# ACBoard.net
KiCad netlist of a schematic drawn in EAGLE
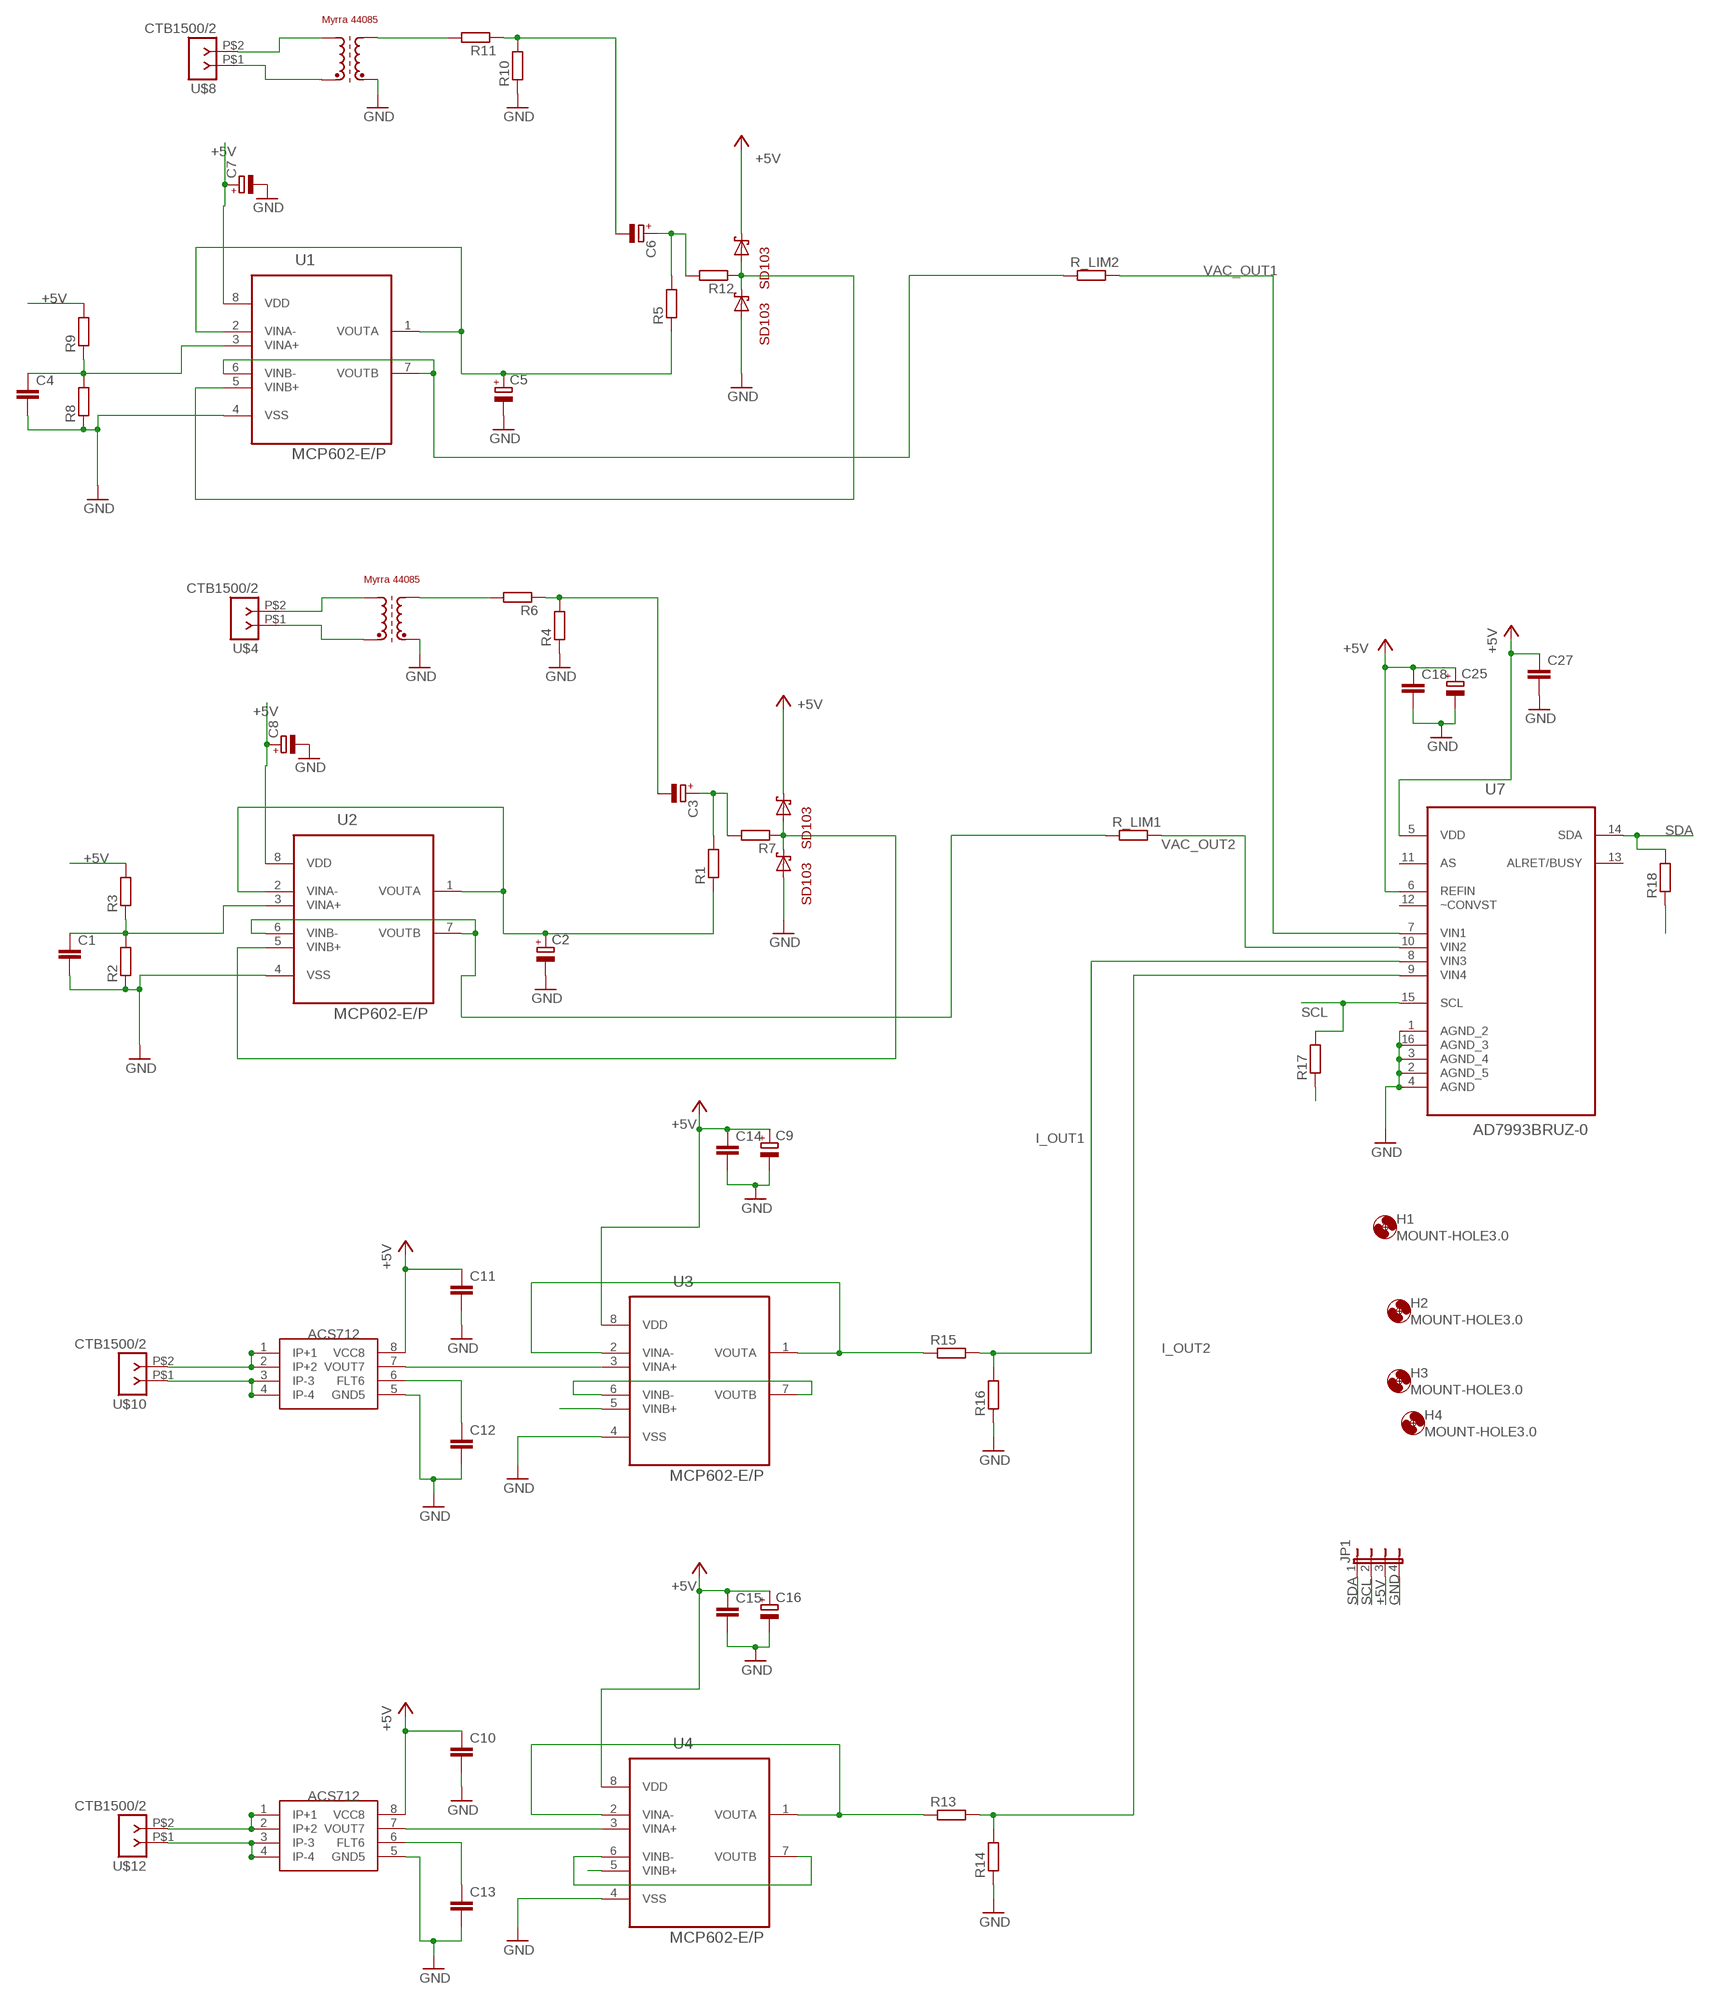
[diagram p0: schematic, sheet 1]

(export (version "E")
  (design (tool "Eeschema 10.0.6"))
  (components
    (comp (ref "C1")
      (value "C5P")
      (footprint "eagle-import:C050-030-075")
      (libsource (lib "eagle-import") (part "C5P"))
    )
    (comp (ref "C2")
      (value "CPOL1")
      (footprint "eagle-import:E2,5-7---100UF")
      (libsource (lib "eagle-import") (part "CPOL1"))
    )
    (comp (ref "C3")
      (value "CPOL1")
      (footprint "eagle-import:E2,5-7---100UF")
      (libsource (lib "eagle-import") (part "CPOL1"))
    )
    (comp (ref "C4")
      (value "C5P")
      (footprint "eagle-import:C050-030-075")
      (libsource (lib "eagle-import") (part "C5P"))
    )
    (comp (ref "C5")
      (value "CPOL1")
      (footprint "eagle-import:E2,5-7---100UF")
      (libsource (lib "eagle-import") (part "CPOL1"))
    )
    (comp (ref "C6")
      (value "CPOL1")
      (footprint "eagle-import:E2,5-7---100UF")
      (libsource (lib "eagle-import") (part "CPOL1"))
    )
    (comp (ref "C7")
      (value "CPOL1")
      (footprint "eagle-import:E2,5-7---100UF")
      (libsource (lib "eagle-import") (part "CPOL1"))
    )
    (comp (ref "C8")
      (value "CPOL1")
      (footprint "eagle-import:E2,5-7---100UF")
      (libsource (lib "eagle-import") (part "CPOL1"))
    )
    (comp (ref "C9")
      (value "CPOL-EUE2-4")
      (footprint "eagle-import:E2-4")
      (libsource (lib "eagle-import") (part "CPOL-EUE2-4"))
    )
    (comp (ref "C10")
      (value "C-EU025-024X044")
      (footprint "eagle-import:C025-024X044")
      (libsource (lib "eagle-import") (part "C-EU025-024X044"))
    )
    (comp (ref "C11")
      (value "C-EU025-024X044")
      (footprint "eagle-import:C025-024X044")
      (libsource (lib "eagle-import") (part "C-EU025-024X044"))
    )
    (comp (ref "C12")
      (value "C-EU025-024X044")
      (footprint "eagle-import:C025-024X044")
      (libsource (lib "eagle-import") (part "C-EU025-024X044"))
    )
    (comp (ref "C13")
      (value "C-EU025-024X044")
      (footprint "eagle-import:C025-024X044")
      (libsource (lib "eagle-import") (part "C-EU025-024X044"))
    )
    (comp (ref "C14")
      (value "C-EU025-024X044")
      (footprint "eagle-import:C025-024X044")
      (libsource (lib "eagle-import") (part "C-EU025-024X044"))
    )
    (comp (ref "C15")
      (value "C-EU025-024X044")
      (footprint "eagle-import:C025-024X044")
      (libsource (lib "eagle-import") (part "C-EU025-024X044"))
    )
    (comp (ref "C16")
      (value "CPOL-EUE2-4")
      (footprint "eagle-import:E2-4")
      (libsource (lib "eagle-import") (part "CPOL-EUE2-4"))
    )
    (comp (ref "C18")
      (value "C-EU025-024X044")
      (footprint "eagle-import:C025-024X044")
      (libsource (lib "eagle-import") (part "C-EU025-024X044"))
    )
    (comp (ref "C25")
      (value "CPOL-EUE2-4")
      (footprint "eagle-import:E2-4")
      (libsource (lib "eagle-import") (part "CPOL-EUE2-4"))
    )
    (comp (ref "C27")
      (value "C-EU025-025X050")
      (footprint "eagle-import:C025-025X050")
      (libsource (lib "eagle-import") (part "C-EU025-025X050"))
    )
    (comp (ref "H1")
      (value "MOUNT-HOLE3.0")
      (footprint "eagle-import:3,0")
      (libsource (lib "eagle-import") (part "MOUNT-HOLE3.0"))
    )
    (comp (ref "H2")
      (value "MOUNT-HOLE3.0")
      (footprint "eagle-import:3,0")
      (libsource (lib "eagle-import") (part "MOUNT-HOLE3.0"))
    )
    (comp (ref "H3")
      (value "MOUNT-HOLE3.0")
      (footprint "eagle-import:3,0")
      (libsource (lib "eagle-import") (part "MOUNT-HOLE3.0"))
    )
    (comp (ref "H4")
      (value "MOUNT-HOLE3.0")
      (footprint "eagle-import:3,0")
      (libsource (lib "eagle-import") (part "MOUNT-HOLE3.0"))
    )
    (comp (ref "JP1")
      (value "JP4E")
      (footprint "eagle-import:JP4")
      (libsource (lib "eagle-import") (part "JP4E"))
    )
    (comp (ref "R1")
      (value "R")
      (footprint "eagle-import:0207_10")
      (libsource (lib "eagle-import") (part "R"))
    )
    (comp (ref "R2")
      (value "R")
      (footprint "eagle-import:0207_10")
      (libsource (lib "eagle-import") (part "R"))
    )
    (comp (ref "R3")
      (value "R")
      (footprint "eagle-import:0207_10")
      (libsource (lib "eagle-import") (part "R"))
    )
    (comp (ref "R4")
      (value "R")
      (footprint "eagle-import:0207_10")
      (libsource (lib "eagle-import") (part "R"))
    )
    (comp (ref "R5")
      (value "R")
      (footprint "eagle-import:0207_10")
      (libsource (lib "eagle-import") (part "R"))
    )
    (comp (ref "R6")
      (value "R")
      (footprint "eagle-import:0207_10")
      (libsource (lib "eagle-import") (part "R"))
    )
    (comp (ref "R7")
      (value "R")
      (footprint "eagle-import:0207_10")
      (libsource (lib "eagle-import") (part "R"))
    )
    (comp (ref "R8")
      (value "R")
      (footprint "eagle-import:0207_10")
      (libsource (lib "eagle-import") (part "R"))
    )
    (comp (ref "R9")
      (value "R")
      (footprint "eagle-import:0207_10")
      (libsource (lib "eagle-import") (part "R"))
    )
    (comp (ref "R10")
      (value "R")
      (footprint "eagle-import:0207_10")
      (libsource (lib "eagle-import") (part "R"))
    )
    (comp (ref "R11")
      (value "R")
      (footprint "eagle-import:0207_10")
      (libsource (lib "eagle-import") (part "R"))
    )
    (comp (ref "R12")
      (value "R")
      (footprint "eagle-import:0207_10")
      (libsource (lib "eagle-import") (part "R"))
    )
    (comp (ref "R13")
      (value "R-EU_0207/7")
      (footprint "eagle-import:0207_7")
      (libsource (lib "eagle-import") (part "R-EU_0207/7"))
    )
    (comp (ref "R14")
      (value "R-EU_0207/7")
      (footprint "eagle-import:0207_7")
      (libsource (lib "eagle-import") (part "R-EU_0207/7"))
    )
    (comp (ref "R15")
      (value "R-EU_0207/7")
      (footprint "eagle-import:0207_7")
      (libsource (lib "eagle-import") (part "R-EU_0207/7"))
    )
    (comp (ref "R16")
      (value "R-EU_0207/7")
      (footprint "eagle-import:0207_7")
      (libsource (lib "eagle-import") (part "R-EU_0207/7"))
    )
    (comp (ref "R17")
      (value "R-EU_0207/7")
      (footprint "eagle-import:0207_7")
      (libsource (lib "eagle-import") (part "R-EU_0207/7"))
    )
    (comp (ref "R18")
      (value "R-EU_0207/7")
      (footprint "eagle-import:0207_7")
      (libsource (lib "eagle-import") (part "R-EU_0207/7"))
    )
    (comp (ref "R_LIM1")
      (value "R")
      (footprint "eagle-import:0207_10")
      (libsource (lib "eagle-import") (part "R"))
    )
    (comp (ref "R_LIM2")
      (value "R")
      (footprint "eagle-import:0207_10")
      (libsource (lib "eagle-import") (part "R"))
    )
    (comp (ref "U$1")
      (value "MYRRA_4408")
      (footprint "eagle-import:4408")
      (libsource (lib "eagle-import") (part "MYRRA_4408"))
    )
    (comp (ref "U$2")
      (value "SD103A")
      (footprint "eagle-import:D035-10")
      (libsource (lib "eagle-import") (part "SD103A"))
    )
    (comp (ref "U$3")
      (value "SD103A")
      (footprint "eagle-import:D035-10")
      (libsource (lib "eagle-import") (part "SD103A"))
    )
    (comp (ref "U$4")
      (value "CTB1500/2")
      (footprint "eagle-import:CTB1500-2")
      (libsource (lib "eagle-import") (part "CTB1500/2"))
    )
    (comp (ref "U$5")
      (value "MYRRA_4408")
      (footprint "eagle-import:4408")
      (libsource (lib "eagle-import") (part "MYRRA_4408"))
    )
    (comp (ref "U$6")
      (value "SD103A")
      (footprint "eagle-import:D035-10")
      (libsource (lib "eagle-import") (part "SD103A"))
    )
    (comp (ref "U$7")
      (value "SD103A")
      (footprint "eagle-import:D035-10")
      (libsource (lib "eagle-import") (part "SD103A"))
    )
    (comp (ref "U$8")
      (value "CTB1500/2")
      (footprint "eagle-import:CTB1500-2")
      (libsource (lib "eagle-import") (part "CTB1500/2"))
    )
    (comp (ref "U$9")
      (value "ACS712")
      (footprint "eagle-import:SO8")
      (libsource (lib "eagle-import") (part "ACS712"))
    )
    (comp (ref "U$10")
      (value "CTB1500/2")
      (footprint "eagle-import:CTB1500-2")
      (libsource (lib "eagle-import") (part "CTB1500/2"))
    )
    (comp (ref "U$11")
      (value "ACS712")
      (footprint "eagle-import:SO8")
      (libsource (lib "eagle-import") (part "ACS712"))
    )
    (comp (ref "U$12")
      (value "CTB1500/2")
      (footprint "eagle-import:CTB1500-2")
      (libsource (lib "eagle-import") (part "CTB1500/2"))
    )
    (comp (ref "U1")
      (value "MCP602-E/P")
      (footprint "eagle-import:DIP254P762X508-8P")
      (libsource (lib "eagle-import") (part "MCP602-E/P"))
    )
    (comp (ref "U2")
      (value "MCP602-E/P")
      (footprint "eagle-import:DIP254P762X508-8P")
      (libsource (lib "eagle-import") (part "MCP602-E/P"))
    )
    (comp (ref "U3")
      (value "MCP602-E/P")
      (footprint "eagle-import:DIP254P762X508-8P")
      (libsource (lib "eagle-import") (part "MCP602-E/P"))
    )
    (comp (ref "U4")
      (value "MCP602-E/P")
      (footprint "eagle-import:DIP254P762X508-8P")
      (libsource (lib "eagle-import") (part "MCP602-E/P"))
    )
    (comp (ref "U7")
      (value "AD7993BRUZ-0")
      (footprint "eagle-import:SOP65P640X120-16N")
      (libsource (lib "eagle-import") (part "AD7993BRUZ-0"))
    )
  )
  (nets
    (net (code "1") (name "+3V3") (class "Default")
      (node (ref "C10") (pin "1") (pinfunction "1_1") (pintype "passive"))
      (node (ref "C11") (pin "1") (pinfunction "1_1") (pintype "passive"))
      (node (ref "C14") (pin "1") (pinfunction "1_1") (pintype "passive"))
      (node (ref "C15") (pin "1") (pinfunction "1_1") (pintype "passive"))
      (node (ref "C16") (pin "+") (pinfunction "+_+") (pintype "passive"))
      (node (ref "C18") (pin "1") (pinfunction "1_1") (pintype "passive"))
      (node (ref "C25") (pin "+") (pinfunction "+_+") (pintype "passive"))
      (node (ref "C27") (pin "1") (pinfunction "1_1") (pintype "passive"))
      (node (ref "C7") (pin "+") (pinfunction "+_+") (pintype "passive"))
      (node (ref "C8") (pin "+") (pinfunction "+_+") (pintype "passive"))
      (node (ref "C9") (pin "+") (pinfunction "+_+") (pintype "passive"))
      (node (ref "JP1") (pin "3") (pinfunction "3_3") (pintype "passive"))
      (node (ref "R17") (pin "1") (pinfunction "1_1") (pintype "passive"))
      (node (ref "R18") (pin "1") (pinfunction "1_1") (pintype "passive"))
      (node (ref "R3") (pin "2") (pinfunction "2_2") (pintype "passive"))
      (node (ref "R9") (pin "2") (pinfunction "2_2") (pintype "passive"))
      (node (ref "U$11") (pin "8") (pinfunction "VCC8_8") (pintype "power_in"))
      (node (ref "U$2") (pin "C") (pinfunction "C_C") (pintype "passive"))
      (node (ref "U$6") (pin "C") (pinfunction "C_C") (pintype "passive"))
      (node (ref "U$9") (pin "8") (pinfunction "VCC8_8") (pintype "power_in"))
      (node (ref "U1") (pin "8") (pinfunction "VDD_8") (pintype "power_in"))
      (node (ref "U2") (pin "8") (pinfunction "VDD_8") (pintype "power_in"))
      (node (ref "U3") (pin "8") (pinfunction "VDD_8") (pintype "power_in"))
      (node (ref "U4") (pin "8") (pinfunction "VDD_8") (pintype "power_in"))
      (node (ref "U7") (pin "5") (pinfunction "VDD_5") (pintype "power_in"))
      (node (ref "U7") (pin "6") (pinfunction "REFIN_6") (pintype "input"))
    )
    (net (code "2") (name "/I_OUT1") (class "Default")
      (node (ref "R15") (pin "2") (pinfunction "2_2") (pintype "passive"))
      (node (ref "R16") (pin "2") (pinfunction "2_2") (pintype "passive"))
      (node (ref "U7") (pin "8") (pinfunction "VIN3_8") (pintype "input"))
    )
    (net (code "3") (name "/I_OUT2") (class "Default")
      (node (ref "R13") (pin "2") (pinfunction "2_2") (pintype "passive"))
      (node (ref "R14") (pin "2") (pinfunction "2_2") (pintype "passive"))
      (node (ref "U7") (pin "9") (pinfunction "VIN4_9") (pintype "input"))
    )
    (net (code "4") (name "/SCL") (class "Default")
      (node (ref "JP1") (pin "2") (pinfunction "2_2") (pintype "passive"))
      (node (ref "R17") (pin "2") (pinfunction "2_2") (pintype "passive"))
      (node (ref "U7") (pin "15") (pinfunction "SCL_15") (pintype "input"))
    )
    (net (code "5") (name "/SDA") (class "Default")
      (node (ref "JP1") (pin "1") (pinfunction "1_1") (pintype "passive"))
      (node (ref "R18") (pin "2") (pinfunction "2_2") (pintype "passive"))
      (node (ref "U7") (pin "14") (pinfunction "SDA_14") (pintype "bidirectional"))
    )
    (net (code "6") (name "/VAC_OUT1") (class "Default")
      (node (ref "R_LIM2") (pin "2") (pinfunction "2_2") (pintype "passive"))
      (node (ref "U7") (pin "7") (pinfunction "VIN1_7") (pintype "input"))
    )
    (net (code "7") (name "/VAC_OUT2") (class "Default")
      (node (ref "R_LIM1") (pin "2") (pinfunction "2_2") (pintype "passive"))
      (node (ref "U7") (pin "10") (pinfunction "VIN2_10") (pintype "input"))
    )
    (net (code "8") (name "GND") (class "Default")
      (node (ref "C1") (pin "2") (pinfunction "2_2") (pintype "passive"))
      (node (ref "C10") (pin "2") (pinfunction "2_2") (pintype "passive"))
      (node (ref "C11") (pin "2") (pinfunction "2_2") (pintype "passive"))
      (node (ref "C12") (pin "2") (pinfunction "2_2") (pintype "passive"))
      (node (ref "C13") (pin "2") (pinfunction "2_2") (pintype "passive"))
      (node (ref "C14") (pin "2") (pinfunction "2_2") (pintype "passive"))
      (node (ref "C15") (pin "2") (pinfunction "2_2") (pintype "passive"))
      (node (ref "C16") (pin "-") (pinfunction "-_-") (pintype "passive"))
      (node (ref "C18") (pin "2") (pinfunction "2_2") (pintype "passive"))
      (node (ref "C2") (pin "-") (pinfunction "-_-") (pintype "passive"))
      (node (ref "C25") (pin "-") (pinfunction "-_-") (pintype "passive"))
      (node (ref "C27") (pin "2") (pinfunction "2_2") (pintype "passive"))
      (node (ref "C4") (pin "2") (pinfunction "2_2") (pintype "passive"))
      (node (ref "C5") (pin "-") (pinfunction "-_-") (pintype "passive"))
      (node (ref "C7") (pin "-") (pinfunction "-_-") (pintype "passive"))
      (node (ref "C8") (pin "-") (pinfunction "-_-") (pintype "passive"))
      (node (ref "C9") (pin "-") (pinfunction "-_-") (pintype "passive"))
      (node (ref "JP1") (pin "4") (pinfunction "4_4") (pintype "passive"))
      (node (ref "R10") (pin "1") (pinfunction "1_1") (pintype "passive"))
      (node (ref "R14") (pin "1") (pinfunction "1_1") (pintype "passive"))
      (node (ref "R16") (pin "1") (pinfunction "1_1") (pintype "passive"))
      (node (ref "R2") (pin "1") (pinfunction "1_1") (pintype "passive"))
      (node (ref "R4") (pin "1") (pinfunction "1_1") (pintype "passive"))
      (node (ref "R8") (pin "1") (pinfunction "1_1") (pintype "passive"))
      (node (ref "U$1") (pin "PIN9") (pinfunction "E2_PIN9") (pintype "passive"))
      (node (ref "U$11") (pin "5") (pinfunction "GND5_5") (pintype "power_in"))
      (node (ref "U$3") (pin "A") (pinfunction "A_A") (pintype "passive"))
      (node (ref "U$5") (pin "PIN9") (pinfunction "E2_PIN9") (pintype "passive"))
      (node (ref "U$7") (pin "A") (pinfunction "A_A") (pintype "passive"))
      (node (ref "U$9") (pin "5") (pinfunction "GND5_5") (pintype "power_in"))
      (node (ref "U1") (pin "4") (pinfunction "VSS_4") (pintype "power_in"))
      (node (ref "U2") (pin "4") (pinfunction "VSS_4") (pintype "power_in"))
      (node (ref "U3") (pin "4") (pinfunction "VSS_4") (pintype "power_in"))
      (node (ref "U3") (pin "5") (pinfunction "VINB+_5") (pintype "input"))
      (node (ref "U4") (pin "4") (pinfunction "VSS_4") (pintype "power_in"))
      (node (ref "U4") (pin "5") (pinfunction "VINB+_5") (pintype "input"))
      (node (ref "U7") (pin "1") (pinfunction "AGND_2_1") (pintype "passive"))
      (node (ref "U7") (pin "16") (pinfunction "AGND_3_16") (pintype "passive"))
      (node (ref "U7") (pin "2") (pinfunction "AGND_5_2") (pintype "passive"))
      (node (ref "U7") (pin "3") (pinfunction "AGND_4_3") (pintype "passive"))
      (node (ref "U7") (pin "4") (pinfunction "AGND_4") (pintype "passive"))
    )
    (net (code "9") (name "Net-(C3-Pad+)") (class "Default")
      (node (ref "C3") (pin "+") (pinfunction "+_+") (pintype "passive"))
      (node (ref "R1") (pin "2") (pinfunction "2_2") (pintype "passive"))
      (node (ref "R7") (pin "2") (pinfunction "2_2") (pintype "passive"))
    )
    (net (code "10") (name "Net-(C3-Pad-)") (class "Default")
      (node (ref "C3") (pin "-") (pinfunction "-_-") (pintype "passive"))
      (node (ref "R4") (pin "2") (pinfunction "2_2") (pintype "passive"))
      (node (ref "R6") (pin "1") (pinfunction "1_1") (pintype "passive"))
    )
    (net (code "11") (name "Net-(C6-Pad+)") (class "Default")
      (node (ref "C6") (pin "+") (pinfunction "+_+") (pintype "passive"))
      (node (ref "R12") (pin "2") (pinfunction "2_2") (pintype "passive"))
      (node (ref "R5") (pin "2") (pinfunction "2_2") (pintype "passive"))
    )
    (net (code "12") (name "Net-(C6-Pad-)") (class "Default")
      (node (ref "C6") (pin "-") (pinfunction "-_-") (pintype "passive"))
      (node (ref "R10") (pin "2") (pinfunction "2_2") (pintype "passive"))
      (node (ref "R11") (pin "1") (pinfunction "1_1") (pintype "passive"))
    )
    (net (code "13") (name "Net-(U$1-A1)") (class "Default")
      (node (ref "U$1") (pin "PIN5") (pinfunction "A1_PIN5") (pintype "passive"))
      (node (ref "U$4") (pin "P$2") (pinfunction "2_P$2") (pintype "passive"))
    )
    (net (code "14") (name "Net-(U$1-A2)") (class "Default")
      (node (ref "R6") (pin "2") (pinfunction "2_2") (pintype "passive"))
      (node (ref "U$1") (pin "PIN7") (pinfunction "A2_PIN7") (pintype "passive"))
    )
    (net (code "15") (name "Net-(U$1-E1)") (class "Default")
      (node (ref "U$1") (pin "PIN1") (pinfunction "E1_PIN1") (pintype "passive"))
      (node (ref "U$4") (pin "P$1") (pinfunction "1_P$1") (pintype "passive"))
    )
    (net (code "16") (name "Net-(U$5-A1)") (class "Default")
      (node (ref "U$5") (pin "PIN5") (pinfunction "A1_PIN5") (pintype "passive"))
      (node (ref "U$8") (pin "P$2") (pinfunction "2_P$2") (pintype "passive"))
    )
    (net (code "17") (name "Net-(U$5-A2)") (class "Default")
      (node (ref "R11") (pin "2") (pinfunction "2_2") (pintype "passive"))
      (node (ref "U$5") (pin "PIN7") (pinfunction "A2_PIN7") (pintype "passive"))
    )
    (net (code "18") (name "Net-(U$5-E1)") (class "Default")
      (node (ref "U$5") (pin "PIN1") (pinfunction "E1_PIN1") (pintype "passive"))
      (node (ref "U$8") (pin "P$1") (pinfunction "1_P$1") (pintype "passive"))
    )
    (net (code "19") (name "Net-(U$9-FLT6)") (class "Default")
      (node (ref "C12") (pin "1") (pinfunction "1_1") (pintype "passive"))
      (node (ref "U$9") (pin "6") (pinfunction "FLT6_6") (pintype "passive"))
    )
    (net (code "20") (name "Net-(U$9-VOUT7)") (class "Default")
      (node (ref "U$9") (pin "7") (pinfunction "VOUT7_7") (pintype "output"))
      (node (ref "U3") (pin "3") (pinfunction "VINA+_3") (pintype "input"))
    )
    (net (code "21") (name "Net-(U$10-1)") (class "Default")
      (node (ref "U$10") (pin "P$1") (pinfunction "1_P$1") (pintype "passive"))
      (node (ref "U$9") (pin "3") (pinfunction "IP-3_3") (pintype "bidirectional"))
      (node (ref "U$9") (pin "4") (pinfunction "IP-4_4") (pintype "bidirectional"))
    )
    (net (code "22") (name "Net-(U$10-2)") (class "Default")
      (node (ref "U$10") (pin "P$2") (pinfunction "2_P$2") (pintype "passive"))
      (node (ref "U$9") (pin "1") (pinfunction "IP+1_1") (pintype "bidirectional"))
      (node (ref "U$9") (pin "2") (pinfunction "IP+2_2") (pintype "bidirectional"))
    )
    (net (code "23") (name "Net-(U$11-FLT6)") (class "Default")
      (node (ref "C13") (pin "1") (pinfunction "1_1") (pintype "passive"))
      (node (ref "U$11") (pin "6") (pinfunction "FLT6_6") (pintype "passive"))
    )
    (net (code "24") (name "Net-(U$11-IP+1)") (class "Default")
      (node (ref "U$11") (pin "1") (pinfunction "IP+1_1") (pintype "bidirectional"))
      (node (ref "U$11") (pin "2") (pinfunction "IP+2_2") (pintype "bidirectional"))
      (node (ref "U$12") (pin "P$2") (pinfunction "2_P$2") (pintype "passive"))
    )
    (net (code "25") (name "Net-(U$11-IP-3)") (class "Default")
      (node (ref "U$11") (pin "3") (pinfunction "IP-3_3") (pintype "bidirectional"))
      (node (ref "U$11") (pin "4") (pinfunction "IP-4_4") (pintype "bidirectional"))
      (node (ref "U$12") (pin "P$1") (pinfunction "1_P$1") (pintype "passive"))
    )
    (net (code "26") (name "Net-(U$11-VOUT7)") (class "Default")
      (node (ref "U$11") (pin "7") (pinfunction "VOUT7_7") (pintype "output"))
      (node (ref "U4") (pin "3") (pinfunction "VINA+_3") (pintype "input"))
    )
    (net (code "27") (name "Net-(U1-VINA+)") (class "Default")
      (node (ref "C4") (pin "1") (pinfunction "1_1") (pintype "passive"))
      (node (ref "R8") (pin "2") (pinfunction "2_2") (pintype "passive"))
      (node (ref "R9") (pin "1") (pinfunction "1_1") (pintype "passive"))
      (node (ref "U1") (pin "3") (pinfunction "VINA+_3") (pintype "input"))
    )
    (net (code "28") (name "Net-(U1-VINA-)") (class "Default")
      (node (ref "C5") (pin "+") (pinfunction "+_+") (pintype "passive"))
      (node (ref "R5") (pin "1") (pinfunction "1_1") (pintype "passive"))
      (node (ref "U1") (pin "1") (pinfunction "VOUTA_1") (pintype "output"))
      (node (ref "U1") (pin "2") (pinfunction "VINA-_2") (pintype "input"))
    )
    (net (code "29") (name "Net-(U1-VINB+)") (class "Default")
      (node (ref "R12") (pin "1") (pinfunction "1_1") (pintype "passive"))
      (node (ref "U$6") (pin "A") (pinfunction "A_A") (pintype "passive"))
      (node (ref "U$7") (pin "C") (pinfunction "C_C") (pintype "passive"))
      (node (ref "U1") (pin "5") (pinfunction "VINB+_5") (pintype "input"))
    )
    (net (code "30") (name "Net-(U1-VINB-)") (class "Default")
      (node (ref "R_LIM2") (pin "1") (pinfunction "1_1") (pintype "passive"))
      (node (ref "U1") (pin "6") (pinfunction "VINB-_6") (pintype "input"))
      (node (ref "U1") (pin "7") (pinfunction "VOUTB_7") (pintype "output"))
    )
    (net (code "31") (name "Net-(U2-VINA+)") (class "Default")
      (node (ref "C1") (pin "1") (pinfunction "1_1") (pintype "passive"))
      (node (ref "R2") (pin "2") (pinfunction "2_2") (pintype "passive"))
      (node (ref "R3") (pin "1") (pinfunction "1_1") (pintype "passive"))
      (node (ref "U2") (pin "3") (pinfunction "VINA+_3") (pintype "input"))
    )
    (net (code "32") (name "Net-(U2-VINA-)") (class "Default")
      (node (ref "C2") (pin "+") (pinfunction "+_+") (pintype "passive"))
      (node (ref "R1") (pin "1") (pinfunction "1_1") (pintype "passive"))
      (node (ref "U2") (pin "1") (pinfunction "VOUTA_1") (pintype "output"))
      (node (ref "U2") (pin "2") (pinfunction "VINA-_2") (pintype "input"))
    )
    (net (code "33") (name "Net-(U2-VINB+)") (class "Default")
      (node (ref "R7") (pin "1") (pinfunction "1_1") (pintype "passive"))
      (node (ref "U$2") (pin "A") (pinfunction "A_A") (pintype "passive"))
      (node (ref "U$3") (pin "C") (pinfunction "C_C") (pintype "passive"))
      (node (ref "U2") (pin "5") (pinfunction "VINB+_5") (pintype "input"))
    )
    (net (code "34") (name "Net-(U2-VINB-)") (class "Default")
      (node (ref "R_LIM1") (pin "1") (pinfunction "1_1") (pintype "passive"))
      (node (ref "U2") (pin "6") (pinfunction "VINB-_6") (pintype "input"))
      (node (ref "U2") (pin "7") (pinfunction "VOUTB_7") (pintype "output"))
    )
    (net (code "35") (name "Net-(U3-VINA-)") (class "Default")
      (node (ref "R15") (pin "1") (pinfunction "1_1") (pintype "passive"))
      (node (ref "U3") (pin "1") (pinfunction "VOUTA_1") (pintype "output"))
      (node (ref "U3") (pin "2") (pinfunction "VINA-_2") (pintype "input"))
    )
    (net (code "36") (name "Net-(U3-VINB-)") (class "Default")
      (node (ref "U3") (pin "6") (pinfunction "VINB-_6") (pintype "input"))
      (node (ref "U3") (pin "7") (pinfunction "VOUTB_7") (pintype "output"))
    )
    (net (code "37") (name "Net-(U4-VINA-)") (class "Default")
      (node (ref "R13") (pin "1") (pinfunction "1_1") (pintype "passive"))
      (node (ref "U4") (pin "1") (pinfunction "VOUTA_1") (pintype "output"))
      (node (ref "U4") (pin "2") (pinfunction "VINA-_2") (pintype "input"))
    )
    (net (code "38") (name "Net-(U4-VINB-)") (class "Default")
      (node (ref "U4") (pin "6") (pinfunction "VINB-_6") (pintype "input"))
      (node (ref "U4") (pin "7") (pinfunction "VOUTB_7") (pintype "output"))
    )
    (net (code "39") (name "unconnected-(U7-ALRET{slash}BUSY-Pad13)") (class "Default")
      (node (ref "U7") (pin "13") (pinfunction "ALRET/BUSY_13") (pintype "output"))
    )
    (net (code "40") (name "unconnected-(U7-AS-Pad11)") (class "Default")
      (node (ref "U7") (pin "11") (pinfunction "AS_11") (pintype "input"))
    )
    (net (code "41") (name "unconnected-(U7-~{CONVST}-Pad12)") (class "Default")
      (node (ref "U7") (pin "12") (pinfunction "~{CONVST}_12") (pintype "input"))
    )
  )
)
